# Sensor.net
KiCad netlist of a schematic drawn in Altium Designer
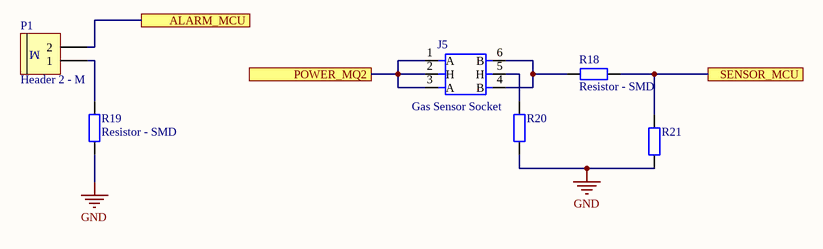
[diagram p0: Sensor.SchDoc]

(export (version "E")
  (design (tool "Eeschema 10.0.6"))
  (components
    (comp (ref "J5")
      (value "Gas Sensor Socket")
      (footprint "MQ2")
      (libsource (lib "My Library") (part "MQ2"))
    )
    (comp (ref "P1")
      (value "Header 2 - M")
      (footprint "Medium - Header 2")
      (description "Header, 2-Pin, Medium")
      (fields (field (name "PUBLISHER") "Altium Limited"))
      (libsource (lib "My Library") (part "Header 2 - M"))
    )
    (comp (ref "R18")
      (value "Resistor - SMD")
      (footprint "RES-SMD-0805")
      (description "Resistor SMD")
      (fields
        (field (name "MANUFACTURER") "Generic Components")
        (field (name "PUBLISHER") "Altium Hobart Technology Centre")
      )
      (libsource (lib "My Library") (part "Resistor - SMD"))
    )
    (comp (ref "R19")
      (value "Resistor - SMD")
      (footprint "RES-SMD-0805")
      (description "Resistor SMD")
      (fields
        (field (name "MANUFACTURER") "Generic Components")
        (field (name "PUBLISHER") "Altium Hobart Technology Centre")
      )
      (libsource (lib "My Library") (part "Resistor - SMD"))
    )
    (comp (ref "R20")
      (value "Resistor - SMD")
      (footprint "RES-SMD-0805")
      (description "Resistor SMD")
      (fields
        (field (name "MANUFACTURER") "Generic Components")
        (field (name "PUBLISHER") "Altium Hobart Technology Centre")
      )
      (libsource (lib "My Library") (part "Resistor - SMD"))
    )
    (comp (ref "R21")
      (value "Resistor - SMD")
      (footprint "RES-SMD-0805")
      (description "Resistor SMD")
      (fields
        (field (name "MANUFACTURER") "Generic Components")
        (field (name "PUBLISHER") "Altium Hobart Technology Centre")
      )
      (libsource (lib "My Library") (part "Resistor - SMD"))
    )
  )
  (nets
    (net (code "1") (name "/ALARM_MCU") (class "Default")
      (node (ref "P1") (pin "2") (pinfunction "2_2") (pintype "passive"))
    )
    (net (code "2") (name "/POWER_MQ2") (class "Default")
      (node (ref "J5") (pin "1") (pinfunction "A_1") (pintype "passive"))
      (node (ref "J5") (pin "2") (pinfunction "H_2") (pintype "passive"))
      (node (ref "J5") (pin "3") (pinfunction "A_3") (pintype "passive"))
    )
    (net (code "3") (name "/SENSOR_MCU") (class "Default")
      (node (ref "R18") (pin "1") (pinfunction "1_1") (pintype "passive"))
      (node (ref "R21") (pin "1") (pinfunction "1_1") (pintype "passive"))
    )
    (net (code "4") (name "GND") (class "Default")
      (node (ref "R19") (pin "2") (pinfunction "2_2") (pintype "passive"))
      (node (ref "R20") (pin "2") (pinfunction "2_2") (pintype "passive"))
      (node (ref "R21") (pin "2") (pinfunction "2_2") (pintype "passive"))
    )
    (net (code "5") (name "Net-(J5-B-Pad4)") (class "Default")
      (node (ref "J5") (pin "4") (pinfunction "B_4") (pintype "passive"))
      (node (ref "J5") (pin "6") (pinfunction "B_6") (pintype "passive"))
      (node (ref "R18") (pin "2") (pinfunction "2_2") (pintype "passive"))
    )
    (net (code "6") (name "Net-(J5-H-Pad5)") (class "Default")
      (node (ref "J5") (pin "5") (pinfunction "H_5") (pintype "passive"))
      (node (ref "R20") (pin "1") (pinfunction "1_1") (pintype "passive"))
    )
    (net (code "7") (name "Net-(P1-Pad1)") (class "Default")
      (node (ref "P1") (pin "1") (pinfunction "1_1") (pintype "passive"))
      (node (ref "R19") (pin "1") (pinfunction "1_1") (pintype "passive"))
    )
  )
)
